# OSSI-1_EPS_1.net
KiCad netlist of a schematic drawn in Altium Designer
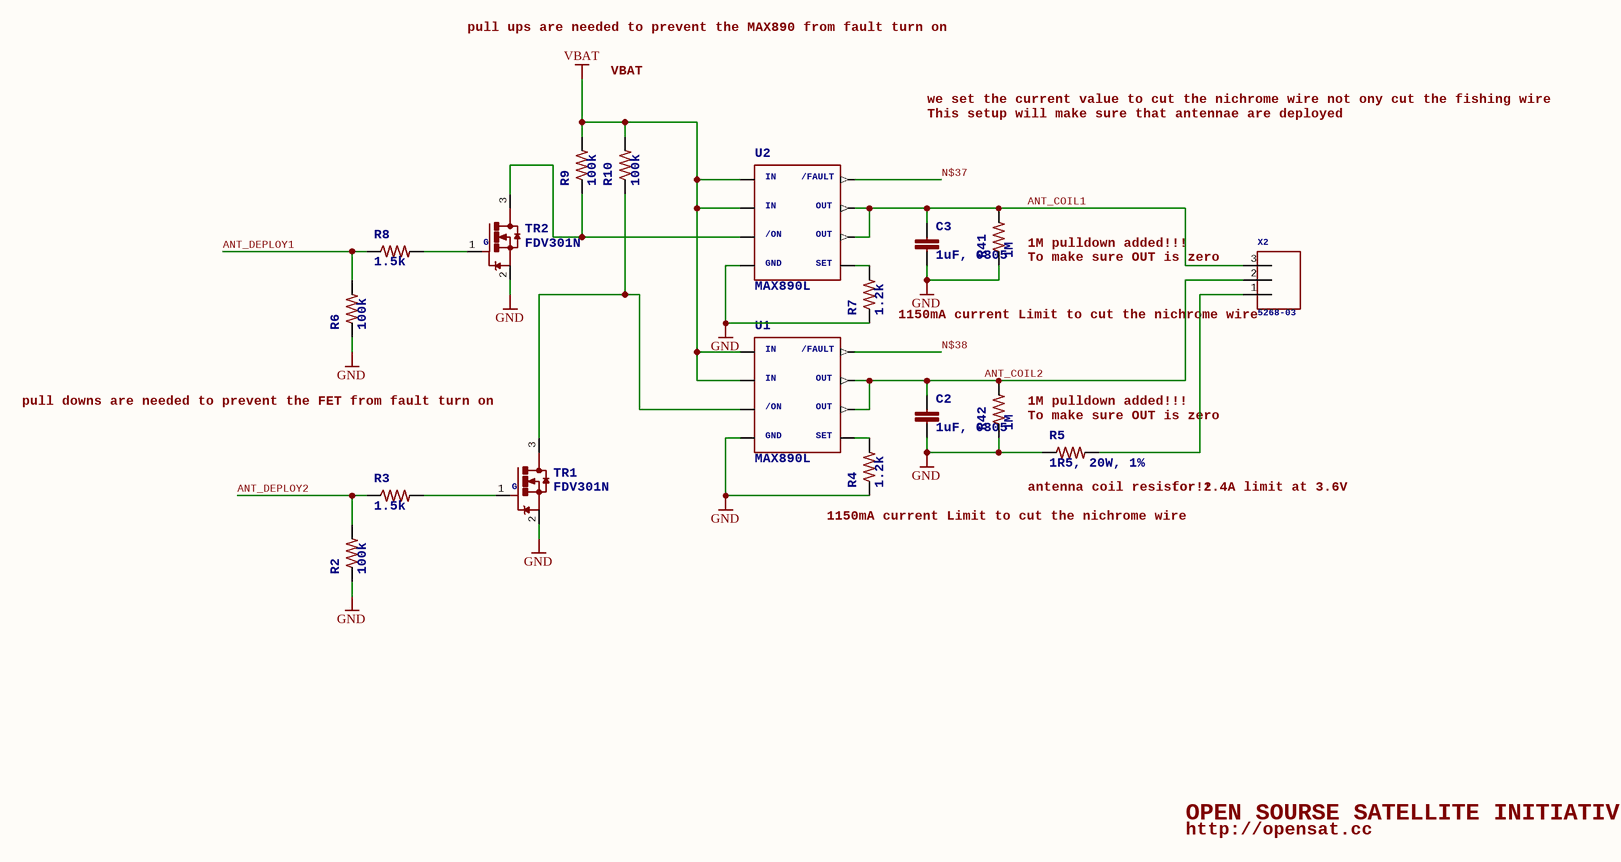
[diagram p0: OSSI-1 EPS_1.SchDoc]

(export (version "E")
  (design (tool "Eeschema 10.0.6"))
  (components
    (comp (ref "C2")
      (value "1uF, 0805")
      (footprint "C0805(2012)")
      (fields (field (name ">NAME") "C2") (field (name ">VALUE") "1uF, 0805"))
      (libsource (lib "OSSI") (part "C0805(2012)"))
    )
    (comp (ref "C3")
      (value "1uF, 0805")
      (footprint "C0805(2012)")
      (fields (field (name ">NAME") "C3") (field (name ">VALUE") "1uF, 0805"))
      (libsource (lib "OSSI") (part "C0805(2012)"))
    )
    (comp (ref "R2")
      (value "100k")
      (footprint "R0603(1608)")
      (fields (field (name ">NAME") "R2") (field (name ">VALUE") "100k"))
      (libsource (lib "OSSI") (part "R0603(1608)"))
    )
    (comp (ref "R3")
      (value "1.5k")
      (footprint "R0603(1608)")
      (fields (field (name ">NAME") "R3") (field (name ">VALUE") "1.5k"))
      (libsource (lib "OSSI") (part "R0603(1608)"))
    )
    (comp (ref "R4")
      (value "1.2k")
      (footprint "R0603(1608)")
      (fields (field (name ">NAME") "R4") (field (name ">VALUE") "1.2k"))
      (libsource (lib "OSSI") (part "R0603(1608)"))
    )
    (comp (ref "R5")
      (value "1R5, 20W, 1%")
      (footprint "PWR263S-20")
      (fields (field (name ">NAME") "R5") (field (name ">VALUE") "1R5, 20W, 1%"))
      (libsource (lib "OSSI") (part "RPWR263S"))
    )
    (comp (ref "R6")
      (value "100k")
      (footprint "R0603(1608)")
      (fields (field (name ">NAME") "R6") (field (name ">VALUE") "100k"))
      (libsource (lib "OSSI") (part "R0603(1608)"))
    )
    (comp (ref "R7")
      (value "1.2k")
      (footprint "R0603(1608)")
      (fields (field (name ">NAME") "R7") (field (name ">VALUE") "1.2k"))
      (libsource (lib "OSSI") (part "R0603(1608)"))
    )
    (comp (ref "R8")
      (value "1.5k")
      (footprint "R0603(1608)")
      (fields (field (name ">NAME") "R8") (field (name ">VALUE") "1.5k"))
      (libsource (lib "OSSI") (part "R0603(1608)"))
    )
    (comp (ref "R9")
      (value "100k")
      (footprint "R0603(1608)")
      (fields (field (name ">NAME") "R9") (field (name ">VALUE") "100k"))
      (libsource (lib "OSSI") (part "R0603(1608)"))
    )
    (comp (ref "R10")
      (value "100k")
      (footprint "R0603(1608)")
      (fields (field (name ">NAME") "R10") (field (name ">VALUE") "100k"))
      (libsource (lib "OSSI") (part "R0603(1608)"))
    )
    (comp (ref "R41")
      (value "1M")
      (footprint "R0603(1608)")
      (fields (field (name ">NAME") "R41") (field (name ">VALUE") "1M"))
      (libsource (lib "OSSI") (part "R0603(1608)"))
    )
    (comp (ref "R42")
      (value "1M")
      (footprint "R0603(1608)")
      (fields (field (name ">NAME") "R42") (field (name ">VALUE") "1M"))
      (libsource (lib "OSSI") (part "R0603(1608)"))
    )
    (comp (ref "TR1")
      (value "FDV301N")
      (footprint "SOT23")
      (description "FDV301N Digital N channel - FET / Rdson = 5 Ohm / Vgs = 0.7~1.06V / Ids = 220mA")
      (fields (field (name "G") "G") (field (name ">NAME") "TR1") (field (name ">VALUE") "FDV301N"))
      (libsource (lib "OSSI") (part "FDV301N"))
    )
    (comp (ref "TR2")
      (value "FDV301N")
      (footprint "SOT23")
      (description "FDV301N Digital N channel - FET / Rdson = 5 Ohm / Vgs = 0.7~1.06V / Ids = 220mA")
      (fields (field (name "G") "G") (field (name ">NAME") "TR2") (field (name ">VALUE") "FDV301N"))
      (libsource (lib "OSSI") (part "FDV301N"))
    )
    (comp (ref "U1")
      (value "MAX890L")
      (footprint "SO8")
      (fields
        (field (name "IN") "IN")
        (field (name "IN_1") "IN")
        (field (name "/ON") "/ON")
        (field (name "GND") "GND")
        (field (name "SET") "SET")
        (field (name "OUT") "OUT")
        (field (name "OUT_1") "OUT")
        (field (name "/FAULT") "/FAULT")
        (field (name ">NAME") "U1")
        (field (name ">VALUE") "MAX890L")
      )
      (libsource (lib "OSSI") (part "MAX890L"))
    )
    (comp (ref "U2")
      (value "MAX890L")
      (footprint "SO8")
      (fields
        (field (name "IN") "IN")
        (field (name "IN_1") "IN")
        (field (name "/ON") "/ON")
        (field (name "GND") "GND")
        (field (name "SET") "SET")
        (field (name "OUT") "OUT")
        (field (name "OUT_1") "OUT")
        (field (name "/FAULT") "/FAULT")
        (field (name ">NAME") "U2")
        (field (name ">VALUE") "MAX890L")
      )
      (libsource (lib "OSSI") (part "MAX890L"))
    )
    (comp (ref "X2")
      (value "5268-03")
      (footprint "5268-03")
      (fields (field (name ">NAME") "X2") (field (name ">VALUE") "5268-03"))
      (libsource (lib "OSSI") (part "5268-03"))
    )
  )
  (nets
    (net (code "1") (name "/ANT_COIL1") (class "Default")
      (node (ref "C3") (pin "1") (pinfunction "1_1") (pintype "passive"))
      (node (ref "R41") (pin "2") (pinfunction "2_2") (pintype "passive"))
      (node (ref "U2") (pin "6") (pinfunction "P$6_6") (pintype "output"))
      (node (ref "U2") (pin "7") (pinfunction "P$7_7") (pintype "output"))
      (node (ref "X2") (pin "3") (pinfunction "3_3") (pintype "passive"))
    )
    (net (code "2") (name "/ANT_COIL2") (class "Default")
      (node (ref "C2") (pin "1") (pinfunction "1_1") (pintype "passive"))
      (node (ref "R42") (pin "2") (pinfunction "2_2") (pintype "passive"))
      (node (ref "U1") (pin "6") (pinfunction "P$6_6") (pintype "output"))
      (node (ref "U1") (pin "7") (pinfunction "P$7_7") (pintype "output"))
      (node (ref "X2") (pin "2") (pinfunction "2_2") (pintype "passive"))
    )
    (net (code "3") (name "/ANT_DEPLOY1") (class "Default")
      (node (ref "R6") (pin "2") (pinfunction "2_2") (pintype "passive"))
      (node (ref "R8") (pin "1") (pinfunction "1_1") (pintype "passive"))
    )
    (net (code "4") (name "/ANT_DEPLOY2") (class "Default")
      (node (ref "R2") (pin "2") (pinfunction "2_2") (pintype "passive"))
      (node (ref "R3") (pin "1") (pinfunction "1_1") (pintype "passive"))
    )
    (net (code "5") (name "/N$37") (class "Default")
      (node (ref "U2") (pin "8") (pinfunction "P$8_8") (pintype "output"))
    )
    (net (code "6") (name "/N$38") (class "Default")
      (node (ref "U1") (pin "8") (pinfunction "P$8_8") (pintype "output"))
    )
    (net (code "7") (name "GND") (class "Default")
      (node (ref "C2") (pin "2") (pinfunction "2_2") (pintype "passive"))
      (node (ref "C3") (pin "2") (pinfunction "2_2") (pintype "passive"))
      (node (ref "R2") (pin "1") (pinfunction "1_1") (pintype "passive"))
      (node (ref "R4") (pin "1") (pinfunction "1_1") (pintype "passive"))
      (node (ref "R41") (pin "1") (pinfunction "1_1") (pintype "passive"))
      (node (ref "R42") (pin "1") (pinfunction "1_1") (pintype "passive"))
      (node (ref "R5") (pin "P$1") (pinfunction "1_P$1") (pintype "passive"))
      (node (ref "R6") (pin "1") (pinfunction "1_1") (pintype "passive"))
      (node (ref "R7") (pin "1") (pinfunction "1_1") (pintype "passive"))
      (node (ref "TR1") (pin "2") (pinfunction "S_2") (pintype "passive"))
      (node (ref "TR2") (pin "2") (pinfunction "S_2") (pintype "passive"))
      (node (ref "U1") (pin "4") (pinfunction "P$4_4") (pintype "power_in"))
      (node (ref "U2") (pin "4") (pinfunction "P$4_4") (pintype "power_in"))
    )
    (net (code "8") (name "Net-(R5-2)") (class "Default")
      (node (ref "R5") (pin "P$2") (pinfunction "2_P$2") (pintype "passive"))
      (node (ref "X2") (pin "1") (pinfunction "1_1") (pintype "passive"))
    )
    (net (code "9") (name "Net-(TR1-D)") (class "Default")
      (node (ref "R10") (pin "1") (pinfunction "1_1") (pintype "passive"))
      (node (ref "TR1") (pin "3") (pinfunction "D_3") (pintype "passive"))
      (node (ref "U1") (pin "3") (pinfunction "P$3_3") (pintype "passive"))
    )
    (net (code "10") (name "Net-(TR1-G)") (class "Default")
      (node (ref "R3") (pin "2") (pinfunction "2_2") (pintype "passive"))
      (node (ref "TR1") (pin "1") (pinfunction "G_1") (pintype "passive"))
    )
    (net (code "11") (name "Net-(TR2-D)") (class "Default")
      (node (ref "R9") (pin "1") (pinfunction "1_1") (pintype "passive"))
      (node (ref "TR2") (pin "3") (pinfunction "D_3") (pintype "passive"))
      (node (ref "U2") (pin "3") (pinfunction "P$3_3") (pintype "passive"))
    )
    (net (code "12") (name "Net-(TR2-G)") (class "Default")
      (node (ref "R8") (pin "2") (pinfunction "2_2") (pintype "passive"))
      (node (ref "TR2") (pin "1") (pinfunction "G_1") (pintype "passive"))
    )
    (net (code "13") (name "Net-(U1-P$5)") (class "Default")
      (node (ref "R4") (pin "2") (pinfunction "2_2") (pintype "passive"))
      (node (ref "U1") (pin "5") (pinfunction "P$5_5") (pintype "passive"))
    )
    (net (code "14") (name "Net-(U2-P$5)") (class "Default")
      (node (ref "R7") (pin "2") (pinfunction "2_2") (pintype "passive"))
      (node (ref "U2") (pin "5") (pinfunction "P$5_5") (pintype "passive"))
    )
    (net (code "15") (name "VBAT") (class "Default")
      (node (ref "R10") (pin "2") (pinfunction "2_2") (pintype "passive"))
      (node (ref "R9") (pin "2") (pinfunction "2_2") (pintype "passive"))
      (node (ref "U1") (pin "1") (pinfunction "P$1_1") (pintype "passive"))
      (node (ref "U1") (pin "2") (pinfunction "P$2_2") (pintype "passive"))
      (node (ref "U2") (pin "1") (pinfunction "P$1_1") (pintype "passive"))
      (node (ref "U2") (pin "2") (pinfunction "P$2_2") (pintype "passive"))
    )
  )
)
